# PP_Schematic.net
KiCad netlist of a schematic drawn in Altium Designer
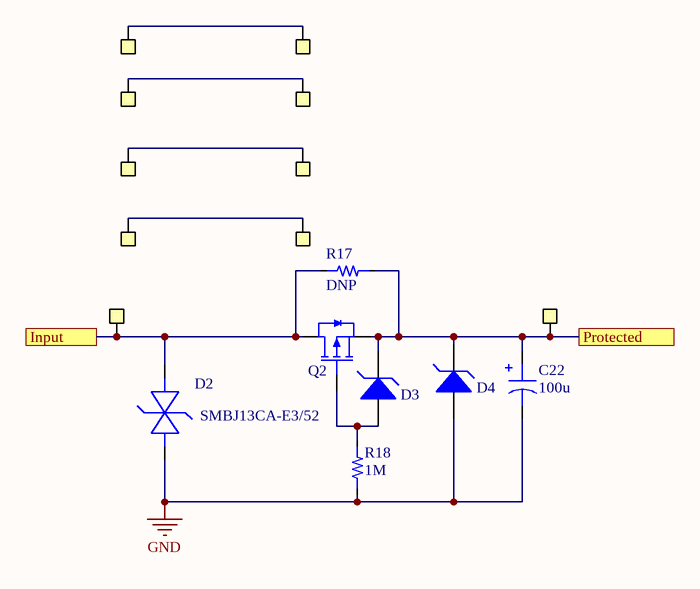
[diagram p0: PP_Schematic.SchDoc]

(export (version "E")
  (design (tool "Eeschema 10.0.6"))
  (components
    (comp (ref "C22")
      (value "100u")
      (footprint "6.60x6.60x8.00mm_E_CAP")
      (description "CAP ALUM 100UF 20% 16V SMD")
      (fields (field (name "Comment") "865080343009"))
      (libsource (lib "Capacitors") (part "865080343009"))
    )
    (comp (ref "D2")
      (value "SMBJ13CA-E3/52")
      (footprint "SMBJ13CA-E3/52")
      (description "21.5V Clamp 27.9A Ipp Tvs Diode Surface Mount DO-214AA (SMBJ). Bidirectional")
      (libsource (lib "Diodes") (part "SMBJ13CA-E3/52"))
    )
    (comp (ref "D3")
      (value "MMSZ5231B-7-F")
      (footprint "SOD-123")
      (description "Zener Diode 5.1V 500mW ±5% Surface Mount SOD-123")
      (libsource (lib "Diodes") (part "MMSZ5231B-7-F"))
    )
    (comp (ref "D4")
      (value "MMSZ5231B-7-F")
      (footprint "SOD-123")
      (description "Zener Diode 5.1V 500mW ±5% Surface Mount SOD-123")
      (libsource (lib "Diodes") (part "MMSZ5231B-7-F"))
    )
    (comp (ref "Q2")
      (value "MOSFET P-CH 30V 2A SOT-23")
      (footprint "SOT23-3")
      (description "P-Channel 2A (Ta) 350mW (Tc) Surface Mount SOT-23")
      (libsource (lib "FETs") (part "STR2P3LLH6"))
    )
    (comp (ref "R17")
      (value "DNP")
      (footprint "0603_RES")
      (fields (field (name "Comment") "Resistor"))
      (libsource (lib "Resistors") (part "Resistor"))
    )
    (comp (ref "R18")
      (value "1M")
      (footprint "0603_RES")
      (fields (field (name "Comment") "Resistor"))
      (libsource (lib "Resistors") (part "Resistor"))
    )
    (comp (ref "X1")
      (value "GenericPinHeader(0.1in)")
      (footprint "GenericPinHeader(.1in)")
      (description "Generic .1in(2.54mm) pitch pin header")
      (libsource (lib "") (part "GenericPinHeader(0.1in)_1"))
    )
    (comp (ref "X2")
      (value "GenericPinHeader(0.1in)")
      (footprint "GenericPinHeader(.1in)")
      (description "Generic .1in(2.54mm) pitch pin header")
      (libsource (lib "") (part "GenericPinHeader(0.1in)_1"))
    )
    (comp (ref "X3")
      (value "GenericPinHeader(0.1in)")
      (footprint "GenericPinHeader(.1in)")
      (description "Generic .1in(2.54mm) pitch pin header")
      (libsource (lib "Connectors") (part "GenericPinHeader(0.1in)"))
    )
    (comp (ref "X4")
      (value "GenericPinHeader(0.1in)")
      (footprint "GenericPinHeader(.1in)")
      (description "Generic .1in(2.54mm) pitch pin header")
      (libsource (lib "Connectors") (part "GenericPinHeader(0.1in)"))
    )
    (comp (ref "X5")
      (value "GenericPinHeader(0.1in)")
      (footprint "GenericPinHeader(.1in)")
      (description "Generic .1in(2.54mm) pitch pin header")
      (libsource (lib "Connectors") (part "GenericPinHeader(0.1in)"))
    )
    (comp (ref "X6")
      (value "GenericPinHeader(0.1in)")
      (footprint "GenericPinHeader(.1in)")
      (description "Generic .1in(2.54mm) pitch pin header")
      (libsource (lib "Connectors") (part "GenericPinHeader(0.1in)"))
    )
    (comp (ref "X7")
      (value "GenericPinHeader(0.1in)")
      (footprint "GenericPinHeader(.1in)")
      (description "Generic .1in(2.54mm) pitch pin header")
      (libsource (lib "Connectors") (part "GenericPinHeader(0.1in)"))
    )
    (comp (ref "X8")
      (value "GenericPinHeader(0.1in)")
      (footprint "GenericPinHeader(.1in)")
      (description "Generic .1in(2.54mm) pitch pin header")
      (libsource (lib "Connectors") (part "GenericPinHeader(0.1in)"))
    )
    (comp (ref "X9")
      (value "GenericPinHeader(0.1in)")
      (footprint "GenericPinHeader(.1in)")
      (description "Generic .1in(2.54mm) pitch pin header")
      (libsource (lib "Connectors") (part "GenericPinHeader(0.1in)"))
    )
    (comp (ref "X10")
      (value "GenericPinHeader(0.1in)")
      (footprint "GenericPinHeader(.1in)")
      (description "Generic .1in(2.54mm) pitch pin header")
      (libsource (lib "Connectors") (part "GenericPinHeader(0.1in)"))
    )
  )
  (nets
    (net (code "1") (name "/Input") (class "Default")
      (node (ref "D2") (pin "2") (pinfunction "2_2") (pintype "passive"))
      (node (ref "Q2") (pin "3") (pinfunction "D_3") (pintype "passive"))
      (node (ref "R17") (pin "1") (pinfunction "1_1") (pintype "passive"))
      (node (ref "X1") (pin "1") (pinfunction "Pin_1") (pintype "passive"))
    )
    (net (code "2") (name "/Protected") (class "Default")
      (node (ref "C22") (pin "1") (pinfunction "1_1") (pintype "passive"))
      (node (ref "D3") (pin "1") (pinfunction "K_1") (pintype "passive"))
      (node (ref "D4") (pin "1") (pinfunction "K_1") (pintype "passive"))
      (node (ref "Q2") (pin "2") (pinfunction "S_2") (pintype "passive"))
      (node (ref "R17") (pin "2") (pinfunction "2_2") (pintype "passive"))
      (node (ref "X2") (pin "1") (pinfunction "Pin_1") (pintype "passive"))
    )
    (net (code "3") (name "GND") (class "Default")
      (node (ref "C22") (pin "2") (pinfunction "2_2") (pintype "passive"))
      (node (ref "D2") (pin "1") (pinfunction "1_1") (pintype "passive"))
      (node (ref "D4") (pin "2") (pinfunction "A_2") (pintype "passive"))
      (node (ref "R18") (pin "1") (pinfunction "1_1") (pintype "passive"))
    )
    (net (code "4") (name "Net-(D3-A)") (class "Default")
      (node (ref "D3") (pin "2") (pinfunction "A_2") (pintype "passive"))
      (node (ref "Q2") (pin "1") (pinfunction "G_1") (pintype "passive"))
      (node (ref "R18") (pin "2") (pinfunction "2_2") (pintype "passive"))
    )
    (net (code "5") (name "Net-(X3-Pin)") (class "Default")
      (node (ref "X3") (pin "1") (pinfunction "Pin_1") (pintype "passive"))
      (node (ref "X4") (pin "1") (pinfunction "Pin_1") (pintype "passive"))
    )
    (net (code "6") (name "Net-(X5-Pin)") (class "Default")
      (node (ref "X5") (pin "1") (pinfunction "Pin_1") (pintype "passive"))
      (node (ref "X6") (pin "1") (pinfunction "Pin_1") (pintype "passive"))
    )
    (net (code "7") (name "Net-(X7-Pin)") (class "Default")
      (node (ref "X7") (pin "1") (pinfunction "Pin_1") (pintype "passive"))
      (node (ref "X8") (pin "1") (pinfunction "Pin_1") (pintype "passive"))
    )
    (net (code "8") (name "Net-(X10-Pin)") (class "Default")
      (node (ref "X10") (pin "1") (pinfunction "Pin_1") (pintype "passive"))
      (node (ref "X9") (pin "1") (pinfunction "Pin_1") (pintype "passive"))
    )
  )
)
